# Quick_Fix_Mix.net
KiCad netlist of a schematic drawn in EAGLE
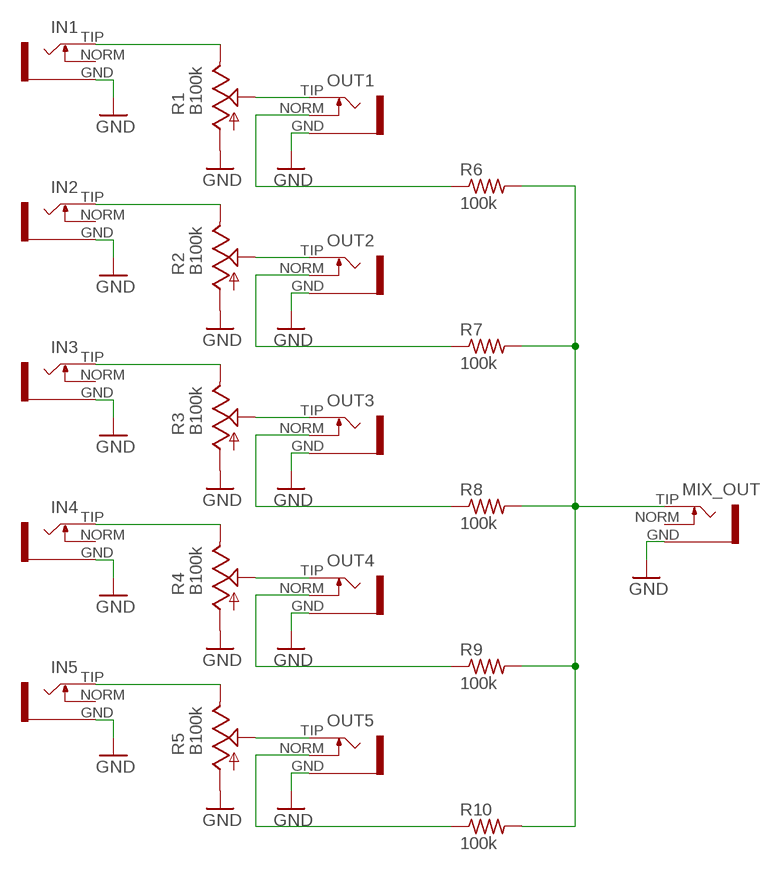
[diagram p0: schematic, sheet 1]

(export (version "E")
  (design (tool "Eeschema 10.0.6"))
  (components
    (comp (ref "IN1")
      (value "INSTRUO_S_JACK_SMALL2")
      (footprint "eagle-import:INSTRUO_S_JACK_SMALL2")
      (libsource (lib "eagle-import") (part "INSTRUO_S_JACK_SMALL2"))
    )
    (comp (ref "IN2")
      (value "INSTRUO_S_JACK_SMALL2")
      (footprint "eagle-import:INSTRUO_S_JACK_SMALL2")
      (libsource (lib "eagle-import") (part "INSTRUO_S_JACK_SMALL2"))
    )
    (comp (ref "IN3")
      (value "INSTRUO_S_JACK_SMALL2")
      (footprint "eagle-import:INSTRUO_S_JACK_SMALL2")
      (libsource (lib "eagle-import") (part "INSTRUO_S_JACK_SMALL2"))
    )
    (comp (ref "IN4")
      (value "INSTRUO_S_JACK_SMALL2")
      (footprint "eagle-import:INSTRUO_S_JACK_SMALL2")
      (libsource (lib "eagle-import") (part "INSTRUO_S_JACK_SMALL2"))
    )
    (comp (ref "IN5")
      (value "INSTRUO_S_JACK_SMALL2")
      (footprint "eagle-import:INSTRUO_S_JACK_SMALL2")
      (libsource (lib "eagle-import") (part "INSTRUO_S_JACK_SMALL2"))
    )
    (comp (ref "MIX_OUT")
      (value "INSTRUO_S_JACK_SMALL2")
      (footprint "eagle-import:INSTRUO_S_JACK_SMALL2")
      (libsource (lib "eagle-import") (part "INSTRUO_S_JACK_SMALL2"))
    )
    (comp (ref "OUT1")
      (value "INSTRUO_S_JACK_S2_INV")
      (footprint "eagle-import:INSTRUO_S_JACK_S2_INV")
      (libsource (lib "eagle-import") (part "INSTRUO_S_JACK_S2_INV"))
    )
    (comp (ref "OUT2")
      (value "INSTRUO_S_JACK_S2_INV")
      (footprint "eagle-import:INSTRUO_S_JACK_S2_INV")
      (libsource (lib "eagle-import") (part "INSTRUO_S_JACK_S2_INV"))
    )
    (comp (ref "OUT3")
      (value "INSTRUO_S_JACK_S2_INV")
      (footprint "eagle-import:INSTRUO_S_JACK_S2_INV")
      (libsource (lib "eagle-import") (part "INSTRUO_S_JACK_S2_INV"))
    )
    (comp (ref "OUT4")
      (value "INSTRUO_S_JACK_S2_INV")
      (footprint "eagle-import:INSTRUO_S_JACK_S2_INV")
      (libsource (lib "eagle-import") (part "INSTRUO_S_JACK_S2_INV"))
    )
    (comp (ref "OUT5")
      (value "INSTRUO_S_JACK_S2_INV")
      (footprint "eagle-import:INSTRUO_S_JACK_S2_INV")
      (libsource (lib "eagle-import") (part "INSTRUO_S_JACK_S2_INV"))
    )
    (comp (ref "R1")
      (value "B100k")
      (footprint "eagle-import:OG-POTS_ALPS_POT_VERTICAL")
      (libsource (lib "eagle-import") (part "OG-POTS_POT_USVERTICAL"))
    )
    (comp (ref "R2")
      (value "B100k")
      (footprint "eagle-import:OG-POTS_ALPS_POT_VERTICAL")
      (libsource (lib "eagle-import") (part "OG-POTS_POT_USVERTICAL"))
    )
    (comp (ref "R3")
      (value "B100k")
      (footprint "eagle-import:OG-POTS_ALPS_POT_VERTICAL")
      (libsource (lib "eagle-import") (part "OG-POTS_POT_USVERTICAL"))
    )
    (comp (ref "R4")
      (value "B100k")
      (footprint "eagle-import:OG-POTS_ALPS_POT_VERTICAL")
      (libsource (lib "eagle-import") (part "OG-POTS_POT_USVERTICAL"))
    )
    (comp (ref "R5")
      (value "B100k")
      (footprint "eagle-import:OG-POTS_ALPS_POT_VERTICAL")
      (libsource (lib "eagle-import") (part "OG-POTS_POT_USVERTICAL"))
    )
    (comp (ref "R6")
      (value "100k")
      (footprint "eagle-import:R0603")
      (libsource (lib "eagle-import") (part "R-US_R0603"))
    )
    (comp (ref "R7")
      (value "100k")
      (footprint "eagle-import:R0603")
      (libsource (lib "eagle-import") (part "R-US_R0603"))
    )
    (comp (ref "R8")
      (value "100k")
      (footprint "eagle-import:R0603")
      (libsource (lib "eagle-import") (part "R-US_R0603"))
    )
    (comp (ref "R9")
      (value "100k")
      (footprint "eagle-import:R0603")
      (libsource (lib "eagle-import") (part "R-US_R0603"))
    )
    (comp (ref "R10")
      (value "100k")
      (footprint "eagle-import:R0603")
      (libsource (lib "eagle-import") (part "R-US_R0603"))
    )
  )
  (nets
    (net (code "1") (name "GND") (class "Default")
      (node (ref "IN1") (pin "GND") (pinfunction "GND_GND") (pintype "passive"))
      (node (ref "IN2") (pin "GND") (pinfunction "GND_GND") (pintype "passive"))
      (node (ref "IN3") (pin "GND") (pinfunction "GND_GND") (pintype "passive"))
      (node (ref "IN4") (pin "GND") (pinfunction "GND_GND") (pintype "passive"))
      (node (ref "IN5") (pin "GND") (pinfunction "GND_GND") (pintype "passive"))
      (node (ref "MIX_OUT") (pin "GND") (pinfunction "GND_GND") (pintype "passive"))
      (node (ref "OUT1") (pin "GND") (pinfunction "GND_GND") (pintype "passive"))
      (node (ref "OUT2") (pin "GND") (pinfunction "GND_GND") (pintype "passive"))
      (node (ref "OUT3") (pin "GND") (pinfunction "GND_GND") (pintype "passive"))
      (node (ref "OUT4") (pin "GND") (pinfunction "GND_GND") (pintype "passive"))
      (node (ref "OUT5") (pin "GND") (pinfunction "GND_GND") (pintype "passive"))
      (node (ref "R1") (pin "P$3") (pinfunction "A_P$3") (pintype "passive"))
      (node (ref "R2") (pin "P$3") (pinfunction "A_P$3") (pintype "passive"))
      (node (ref "R3") (pin "P$3") (pinfunction "A_P$3") (pintype "passive"))
      (node (ref "R4") (pin "P$3") (pinfunction "A_P$3") (pintype "passive"))
      (node (ref "R5") (pin "P$3") (pinfunction "A_P$3") (pintype "passive"))
    )
    (net (code "2") (name "Net-(MIX_OUT-PadTIP)") (class "Default")
      (node (ref "MIX_OUT") (pin "TIP") (pinfunction "TIP_TIP") (pintype "passive"))
      (node (ref "R10") (pin "2") (pinfunction "2_2") (pintype "passive"))
      (node (ref "R6") (pin "2") (pinfunction "2_2") (pintype "passive"))
      (node (ref "R7") (pin "2") (pinfunction "2_2") (pintype "passive"))
      (node (ref "R8") (pin "2") (pinfunction "2_2") (pintype "passive"))
      (node (ref "R9") (pin "2") (pinfunction "2_2") (pintype "passive"))
    )
    (net (code "3") (name "Net-(OUT1-PadNORM)") (class "Default")
      (node (ref "OUT1") (pin "NORM") (pinfunction "NORM_NORM") (pintype "passive"))
      (node (ref "R6") (pin "1") (pinfunction "1_1") (pintype "passive"))
    )
    (net (code "4") (name "Net-(OUT2-PadNORM)") (class "Default")
      (node (ref "OUT2") (pin "NORM") (pinfunction "NORM_NORM") (pintype "passive"))
      (node (ref "R7") (pin "1") (pinfunction "1_1") (pintype "passive"))
    )
    (net (code "5") (name "Net-(OUT3-PadNORM)") (class "Default")
      (node (ref "OUT3") (pin "NORM") (pinfunction "NORM_NORM") (pintype "passive"))
      (node (ref "R8") (pin "1") (pinfunction "1_1") (pintype "passive"))
    )
    (net (code "6") (name "Net-(OUT4-PadNORM)") (class "Default")
      (node (ref "OUT4") (pin "NORM") (pinfunction "NORM_NORM") (pintype "passive"))
      (node (ref "R9") (pin "1") (pinfunction "1_1") (pintype "passive"))
    )
    (net (code "7") (name "Net-(OUT5-PadNORM)") (class "Default")
      (node (ref "OUT5") (pin "NORM") (pinfunction "NORM_NORM") (pintype "passive"))
      (node (ref "R10") (pin "1") (pinfunction "1_1") (pintype "passive"))
    )
    (net (code "8") (name "Net-(R1-E)") (class "Default")
      (node (ref "IN1") (pin "TIP") (pinfunction "TIP_TIP") (pintype "passive"))
      (node (ref "R1") (pin "P$1") (pinfunction "E_P$1") (pintype "passive"))
    )
    (net (code "9") (name "Net-(R1-S)") (class "Default")
      (node (ref "OUT1") (pin "TIP") (pinfunction "TIP_TIP") (pintype "passive"))
      (node (ref "R1") (pin "P$2") (pinfunction "S_P$2") (pintype "passive"))
    )
    (net (code "10") (name "Net-(R2-E)") (class "Default")
      (node (ref "IN2") (pin "TIP") (pinfunction "TIP_TIP") (pintype "passive"))
      (node (ref "R2") (pin "P$1") (pinfunction "E_P$1") (pintype "passive"))
    )
    (net (code "11") (name "Net-(R2-S)") (class "Default")
      (node (ref "OUT2") (pin "TIP") (pinfunction "TIP_TIP") (pintype "passive"))
      (node (ref "R2") (pin "P$2") (pinfunction "S_P$2") (pintype "passive"))
    )
    (net (code "12") (name "Net-(R3-E)") (class "Default")
      (node (ref "IN3") (pin "TIP") (pinfunction "TIP_TIP") (pintype "passive"))
      (node (ref "R3") (pin "P$1") (pinfunction "E_P$1") (pintype "passive"))
    )
    (net (code "13") (name "Net-(R3-S)") (class "Default")
      (node (ref "OUT3") (pin "TIP") (pinfunction "TIP_TIP") (pintype "passive"))
      (node (ref "R3") (pin "P$2") (pinfunction "S_P$2") (pintype "passive"))
    )
    (net (code "14") (name "Net-(R4-E)") (class "Default")
      (node (ref "IN4") (pin "TIP") (pinfunction "TIP_TIP") (pintype "passive"))
      (node (ref "R4") (pin "P$1") (pinfunction "E_P$1") (pintype "passive"))
    )
    (net (code "15") (name "Net-(R4-S)") (class "Default")
      (node (ref "OUT4") (pin "TIP") (pinfunction "TIP_TIP") (pintype "passive"))
      (node (ref "R4") (pin "P$2") (pinfunction "S_P$2") (pintype "passive"))
    )
    (net (code "16") (name "Net-(R5-E)") (class "Default")
      (node (ref "IN5") (pin "TIP") (pinfunction "TIP_TIP") (pintype "passive"))
      (node (ref "R5") (pin "P$1") (pinfunction "E_P$1") (pintype "passive"))
    )
    (net (code "17") (name "Net-(R5-S)") (class "Default")
      (node (ref "OUT5") (pin "TIP") (pinfunction "TIP_TIP") (pintype "passive"))
      (node (ref "R5") (pin "P$2") (pinfunction "S_P$2") (pintype "passive"))
    )
    (net (code "18") (name "unconnected-(IN1-PadNORM)") (class "Default")
      (node (ref "IN1") (pin "NORM") (pinfunction "NORM_NORM") (pintype "passive"))
    )
    (net (code "19") (name "unconnected-(IN2-PadNORM)") (class "Default")
      (node (ref "IN2") (pin "NORM") (pinfunction "NORM_NORM") (pintype "passive"))
    )
    (net (code "20") (name "unconnected-(IN3-PadNORM)") (class "Default")
      (node (ref "IN3") (pin "NORM") (pinfunction "NORM_NORM") (pintype "passive"))
    )
    (net (code "21") (name "unconnected-(IN4-PadNORM)") (class "Default")
      (node (ref "IN4") (pin "NORM") (pinfunction "NORM_NORM") (pintype "passive"))
    )
    (net (code "22") (name "unconnected-(IN5-PadNORM)") (class "Default")
      (node (ref "IN5") (pin "NORM") (pinfunction "NORM_NORM") (pintype "passive"))
    )
    (net (code "23") (name "unconnected-(MIX_OUT-PadNORM)") (class "Default")
      (node (ref "MIX_OUT") (pin "NORM") (pinfunction "NORM_NORM") (pintype "passive"))
    )
  )
)
